# akabeacon.net
KiCad netlist of a schematic drawn in EAGLE
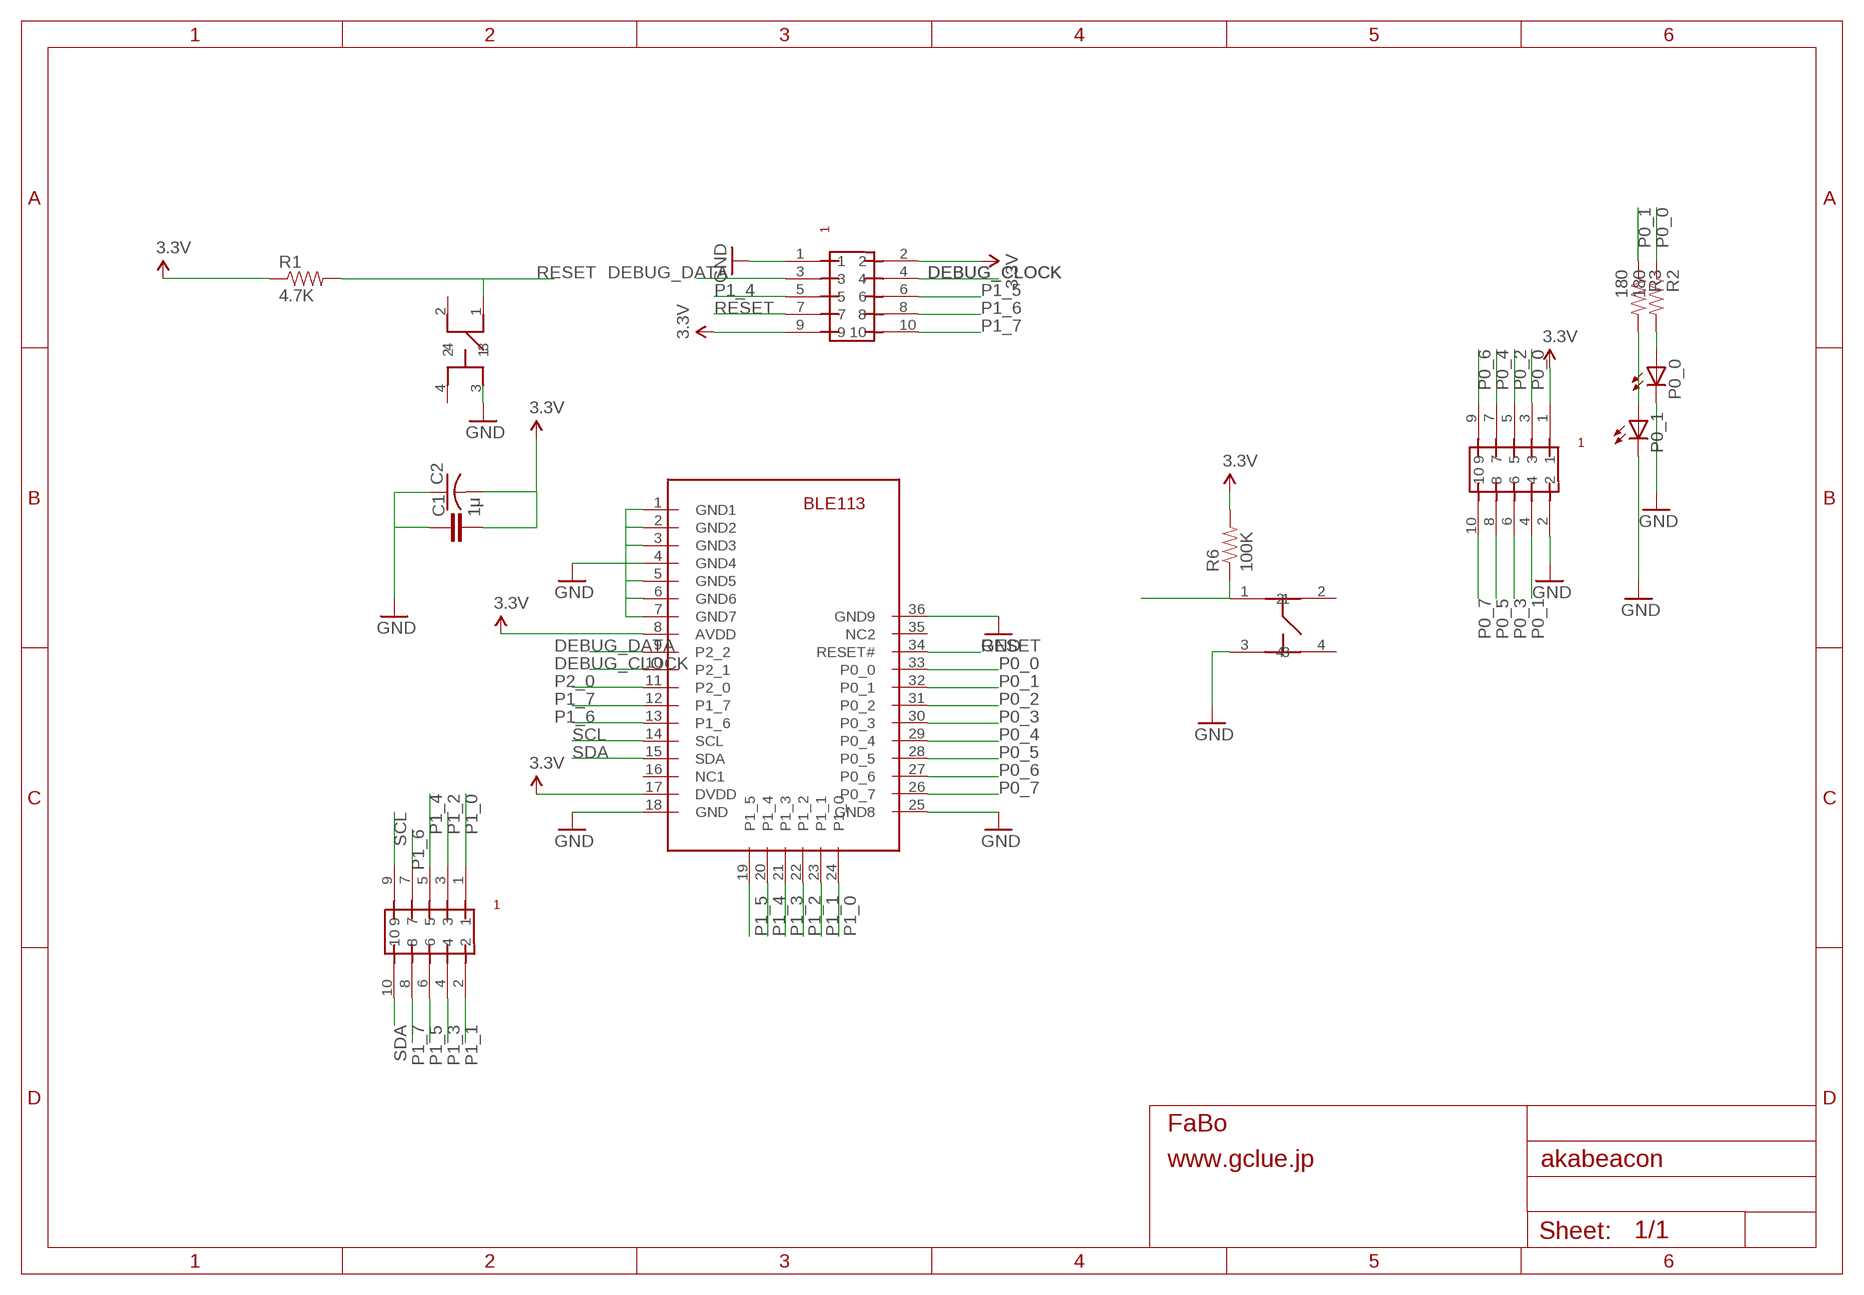
[diagram p0: schematic, sheet 1]

(export (version "E")
  (design (tool "Eeschema 10.0.6"))
  (components
    (comp (ref "C1")
      (value "1μ")
      (footprint "eagle-import:0603-CAP")
      (libsource (lib "eagle-import") (part "CAP0603-CAP"))
    )
    (comp (ref "C2")
      (value "C-USC3225")
      (footprint "eagle-import:C3225")
      (libsource (lib "eagle-import") (part "C-USC3225"))
    )
    (comp (ref "P0_0")
      (value "LEDCHIP-LED0603")
      (footprint "eagle-import:CHIP-LED0603")
      (libsource (lib "eagle-import") (part "LEDCHIP-LED0603"))
    )
    (comp (ref "P0_1")
      (value "LEDCHIP-LED0603")
      (footprint "eagle-import:CHIP-LED0603")
      (libsource (lib "eagle-import") (part "LEDCHIP-LED0603"))
    )
    (comp (ref "R1")
      (value "4.7K")
      (footprint "eagle-import:0603-RES")
      (libsource (lib "eagle-import") (part "RESISTOR0603-RES"))
    )
    (comp (ref "R2")
      (value "180")
      (footprint "eagle-import:0603-RES")
      (libsource (lib "eagle-import") (part "RESISTOR0603-RES"))
    )
    (comp (ref "R3")
      (value "180")
      (footprint "eagle-import:0603-RES")
      (libsource (lib "eagle-import") (part "RESISTOR0603-RES"))
    )
    (comp (ref "R6")
      (value "100K")
      (footprint "eagle-import:0603-RES")
      (libsource (lib "eagle-import") (part "RESISTOR0603-RES"))
    )
    (comp (ref "U$1")
      (value "SWICTH-4P(KMR2)")
      (footprint "eagle-import:SWITCH-4P(KMR2)")
      (libsource (lib "eagle-import") (part "SWICTH-4P(KMR2)"))
    )
    (comp (ref "U$2")
      (value "PIN-HEADER-SMT(1.27MM)2X5")
      (footprint "eagle-import:PIN-HEADER-SMT(1.27MM)2X5")
      (libsource (lib "eagle-import") (part "PIN-HEADER-SMT(1.27MM)2X5"))
    )
    (comp (ref "U$3")
      (value "PIN-HEADER-SMT(1.27MM)2X5")
      (footprint "eagle-import:PIN-HEADER-SMT(1.27MM)2X5")
      (libsource (lib "eagle-import") (part "PIN-HEADER-SMT(1.27MM)2X5"))
    )
    (comp (ref "U$4")
      (value "PIN-HEADER-SMT(1.27MM)2X5")
      (footprint "eagle-import:PIN-HEADER-SMT(1.27MM)2X5")
      (libsource (lib "eagle-import") (part "PIN-HEADER-SMT(1.27MM)2X5"))
    )
    (comp (ref "U$5")
      (value "BLE113")
      (footprint "eagle-import:BLE113")
      (libsource (lib "eagle-import") (part "BLE113"))
    )
    (comp (ref "U$8")
      (value "SWITCH-LS6J2M-T")
      (footprint "eagle-import:SWICTH-LS6J2M-T")
      (libsource (lib "eagle-import") (part "SWITCH-LS6J2M-T"))
    )
  )
  (nets
    (net (code "1") (name "/DEBUG_CLOCK") (class "Default")
      (node (ref "U$2") (pin "4") (pinfunction "4_4") (pintype "bidirectional"))
      (node (ref "U$5") (pin "10") (pinfunction "P2_1_10") (pintype "bidirectional"))
    )
    (net (code "2") (name "/DEBUG_DATA") (class "Default")
      (node (ref "U$2") (pin "3") (pinfunction "3_3") (pintype "bidirectional"))
      (node (ref "U$5") (pin "9") (pinfunction "P2_2_9") (pintype "bidirectional"))
    )
    (net (code "3") (name "/P0_0") (class "Default")
      (node (ref "R2") (pin "1") (pinfunction "1_1") (pintype "passive"))
      (node (ref "U$4") (pin "3") (pinfunction "3_3") (pintype "bidirectional"))
      (node (ref "U$5") (pin "33") (pinfunction "P0_0_33") (pintype "bidirectional"))
    )
    (net (code "4") (name "/P0_1") (class "Default")
      (node (ref "R3") (pin "1") (pinfunction "1_1") (pintype "passive"))
      (node (ref "U$4") (pin "4") (pinfunction "4_4") (pintype "bidirectional"))
      (node (ref "U$5") (pin "32") (pinfunction "P0_1_32") (pintype "bidirectional"))
    )
    (net (code "5") (name "/P0_2") (class "Default")
      (node (ref "U$4") (pin "5") (pinfunction "5_5") (pintype "bidirectional"))
      (node (ref "U$5") (pin "31") (pinfunction "P0_2_31") (pintype "bidirectional"))
    )
    (net (code "6") (name "/P0_3") (class "Default")
      (node (ref "U$4") (pin "6") (pinfunction "6_6") (pintype "bidirectional"))
      (node (ref "U$5") (pin "30") (pinfunction "P0_3_30") (pintype "bidirectional"))
    )
    (net (code "7") (name "/P0_4") (class "Default")
      (node (ref "U$4") (pin "7") (pinfunction "7_7") (pintype "bidirectional"))
      (node (ref "U$5") (pin "29") (pinfunction "P0_4_29") (pintype "bidirectional"))
    )
    (net (code "8") (name "/P0_5") (class "Default")
      (node (ref "U$4") (pin "8") (pinfunction "8_8") (pintype "bidirectional"))
      (node (ref "U$5") (pin "28") (pinfunction "P0_5_28") (pintype "bidirectional"))
    )
    (net (code "9") (name "/P0_6") (class "Default")
      (node (ref "U$4") (pin "9") (pinfunction "9_9") (pintype "bidirectional"))
      (node (ref "U$5") (pin "27") (pinfunction "P0_6_27") (pintype "bidirectional"))
    )
    (net (code "10") (name "/P0_7") (class "Default")
      (node (ref "U$4") (pin "10") (pinfunction "10_10") (pintype "bidirectional"))
      (node (ref "U$5") (pin "26") (pinfunction "P0_7_26") (pintype "bidirectional"))
    )
    (net (code "11") (name "/P1_0") (class "Default")
      (node (ref "U$3") (pin "1") (pinfunction "1_1") (pintype "bidirectional"))
      (node (ref "U$5") (pin "24") (pinfunction "P1_0_24") (pintype "bidirectional"))
    )
    (net (code "12") (name "/P1_1") (class "Default")
      (node (ref "U$3") (pin "2") (pinfunction "2_2") (pintype "bidirectional"))
      (node (ref "U$5") (pin "23") (pinfunction "P1_1_23") (pintype "bidirectional"))
    )
    (net (code "13") (name "/P1_2") (class "Default")
      (node (ref "U$3") (pin "3") (pinfunction "3_3") (pintype "bidirectional"))
      (node (ref "U$5") (pin "22") (pinfunction "P1_2_22") (pintype "bidirectional"))
    )
    (net (code "14") (name "/P1_3") (class "Default")
      (node (ref "U$3") (pin "4") (pinfunction "4_4") (pintype "bidirectional"))
      (node (ref "U$5") (pin "21") (pinfunction "P1_3_21") (pintype "bidirectional"))
    )
    (net (code "15") (name "/P1_4") (class "Default")
      (node (ref "U$2") (pin "5") (pinfunction "5_5") (pintype "bidirectional"))
      (node (ref "U$3") (pin "5") (pinfunction "5_5") (pintype "bidirectional"))
      (node (ref "U$5") (pin "20") (pinfunction "P1_4_20") (pintype "bidirectional"))
    )
    (net (code "16") (name "/P1_5") (class "Default")
      (node (ref "U$2") (pin "6") (pinfunction "6_6") (pintype "bidirectional"))
      (node (ref "U$3") (pin "6") (pinfunction "6_6") (pintype "bidirectional"))
      (node (ref "U$5") (pin "19") (pinfunction "P1_5_19") (pintype "bidirectional"))
    )
    (net (code "17") (name "/P1_6") (class "Default")
      (node (ref "U$2") (pin "8") (pinfunction "8_8") (pintype "bidirectional"))
      (node (ref "U$3") (pin "7") (pinfunction "7_7") (pintype "bidirectional"))
      (node (ref "U$5") (pin "13") (pinfunction "P1_6_13") (pintype "bidirectional"))
    )
    (net (code "18") (name "/P1_7") (class "Default")
      (node (ref "U$2") (pin "10") (pinfunction "10_10") (pintype "bidirectional"))
      (node (ref "U$3") (pin "8") (pinfunction "8_8") (pintype "bidirectional"))
      (node (ref "U$5") (pin "12") (pinfunction "P1_7_12") (pintype "bidirectional"))
    )
    (net (code "19") (name "/P2_0") (class "Default")
      (node (ref "U$5") (pin "11") (pinfunction "P2_0_11") (pintype "bidirectional"))
    )
    (net (code "20") (name "/RESET") (class "Default")
      (node (ref "R1") (pin "2") (pinfunction "2_2") (pintype "passive"))
      (node (ref "U$2") (pin "7") (pinfunction "7_7") (pintype "bidirectional"))
      (node (ref "U$5") (pin "34") (pinfunction "RESET#_34") (pintype "bidirectional"))
      (node (ref "U$8") (pin "1") (pinfunction "1_1") (pintype "bidirectional"))
    )
    (net (code "21") (name "/SCL") (class "Default")
      (node (ref "U$3") (pin "9") (pinfunction "9_9") (pintype "bidirectional"))
      (node (ref "U$5") (pin "14") (pinfunction "SCL_14") (pintype "bidirectional"))
    )
    (net (code "22") (name "/SDA") (class "Default")
      (node (ref "U$3") (pin "10") (pinfunction "10_10") (pintype "bidirectional"))
      (node (ref "U$5") (pin "15") (pinfunction "SDA_15") (pintype "bidirectional"))
    )
    (net (code "23") (name "3.3V") (class "Default")
      (node (ref "C1") (pin "2") (pinfunction "2_2") (pintype "passive"))
      (node (ref "C2") (pin "2") (pinfunction "2_2") (pintype "passive"))
      (node (ref "R1") (pin "1") (pinfunction "1_1") (pintype "passive"))
      (node (ref "R6") (pin "2") (pinfunction "2_2") (pintype "passive"))
      (node (ref "U$2") (pin "2") (pinfunction "2_2") (pintype "bidirectional"))
      (node (ref "U$2") (pin "9") (pinfunction "9_9") (pintype "bidirectional"))
      (node (ref "U$4") (pin "1") (pinfunction "1_1") (pintype "bidirectional"))
      (node (ref "U$5") (pin "17") (pinfunction "DVDD_17") (pintype "bidirectional"))
      (node (ref "U$5") (pin "8") (pinfunction "AVDD_8") (pintype "bidirectional"))
    )
    (net (code "24") (name "GND") (class "Default")
      (node (ref "C1") (pin "1") (pinfunction "1_1") (pintype "passive"))
      (node (ref "C2") (pin "1") (pinfunction "1_1") (pintype "passive"))
      (node (ref "P0_0") (pin "C") (pinfunction "C_C") (pintype "passive"))
      (node (ref "P0_1") (pin "C") (pinfunction "C_C") (pintype "passive"))
      (node (ref "U$1") (pin "3") (pinfunction "3_3") (pintype "bidirectional"))
      (node (ref "U$2") (pin "1") (pinfunction "1_1") (pintype "bidirectional"))
      (node (ref "U$4") (pin "2") (pinfunction "2_2") (pintype "bidirectional"))
      (node (ref "U$5") (pin "1") (pinfunction "GND1_1") (pintype "bidirectional"))
      (node (ref "U$5") (pin "18") (pinfunction "GND_18") (pintype "bidirectional"))
      (node (ref "U$5") (pin "2") (pinfunction "GND2_2") (pintype "bidirectional"))
      (node (ref "U$5") (pin "25") (pinfunction "GND8_25") (pintype "bidirectional"))
      (node (ref "U$5") (pin "3") (pinfunction "GND3_3") (pintype "bidirectional"))
      (node (ref "U$5") (pin "36") (pinfunction "GND9_36") (pintype "bidirectional"))
      (node (ref "U$5") (pin "4") (pinfunction "GND4_4") (pintype "bidirectional"))
      (node (ref "U$5") (pin "5") (pinfunction "GND5_5") (pintype "bidirectional"))
      (node (ref "U$5") (pin "6") (pinfunction "GND6_6") (pintype "bidirectional"))
      (node (ref "U$5") (pin "7") (pinfunction "GND7_7") (pintype "bidirectional"))
      (node (ref "U$8") (pin "3") (pinfunction "3_3") (pintype "bidirectional"))
    )
    (net (code "25") (name "Net-(P0_0-PadA)") (class "Default")
      (node (ref "P0_0") (pin "A") (pinfunction "A_A") (pintype "passive"))
      (node (ref "R2") (pin "2") (pinfunction "2_2") (pintype "passive"))
    )
    (net (code "26") (name "Net-(P0_1-PadA)") (class "Default")
      (node (ref "P0_1") (pin "A") (pinfunction "A_A") (pintype "passive"))
      (node (ref "R3") (pin "2") (pinfunction "2_2") (pintype "passive"))
    )
    (net (code "27") (name "Net-(R6-Pad1)") (class "Default")
      (node (ref "R6") (pin "1") (pinfunction "1_1") (pintype "passive"))
      (node (ref "U$1") (pin "1") (pinfunction "1_1") (pintype "bidirectional"))
    )
    (net (code "28") (name "unconnected-(U$1-Pad2)") (class "Default")
      (node (ref "U$1") (pin "2") (pinfunction "2_2") (pintype "bidirectional"))
    )
    (net (code "29") (name "unconnected-(U$1-Pad4)") (class "Default")
      (node (ref "U$1") (pin "4") (pinfunction "4_4") (pintype "bidirectional"))
    )
    (net (code "30") (name "unconnected-(U$5-NC1-Pad16)") (class "Default")
      (node (ref "U$5") (pin "16") (pinfunction "NC1_16") (pintype "bidirectional"))
    )
    (net (code "31") (name "unconnected-(U$5-NC2-Pad35)") (class "Default")
      (node (ref "U$5") (pin "35") (pinfunction "NC2_35") (pintype "bidirectional"))
    )
    (net (code "32") (name "unconnected-(U$8-Pad2)") (class "Default")
      (node (ref "U$8") (pin "2") (pinfunction "2_2") (pintype "bidirectional"))
    )
    (net (code "33") (name "unconnected-(U$8-Pad4)") (class "Default")
      (node (ref "U$8") (pin "4") (pinfunction "4_4") (pintype "bidirectional"))
    )
  )
)
